# CH32X033SimpleBoard_SCH.net
KiCad netlist of a schematic drawn in EasyEDA Pro
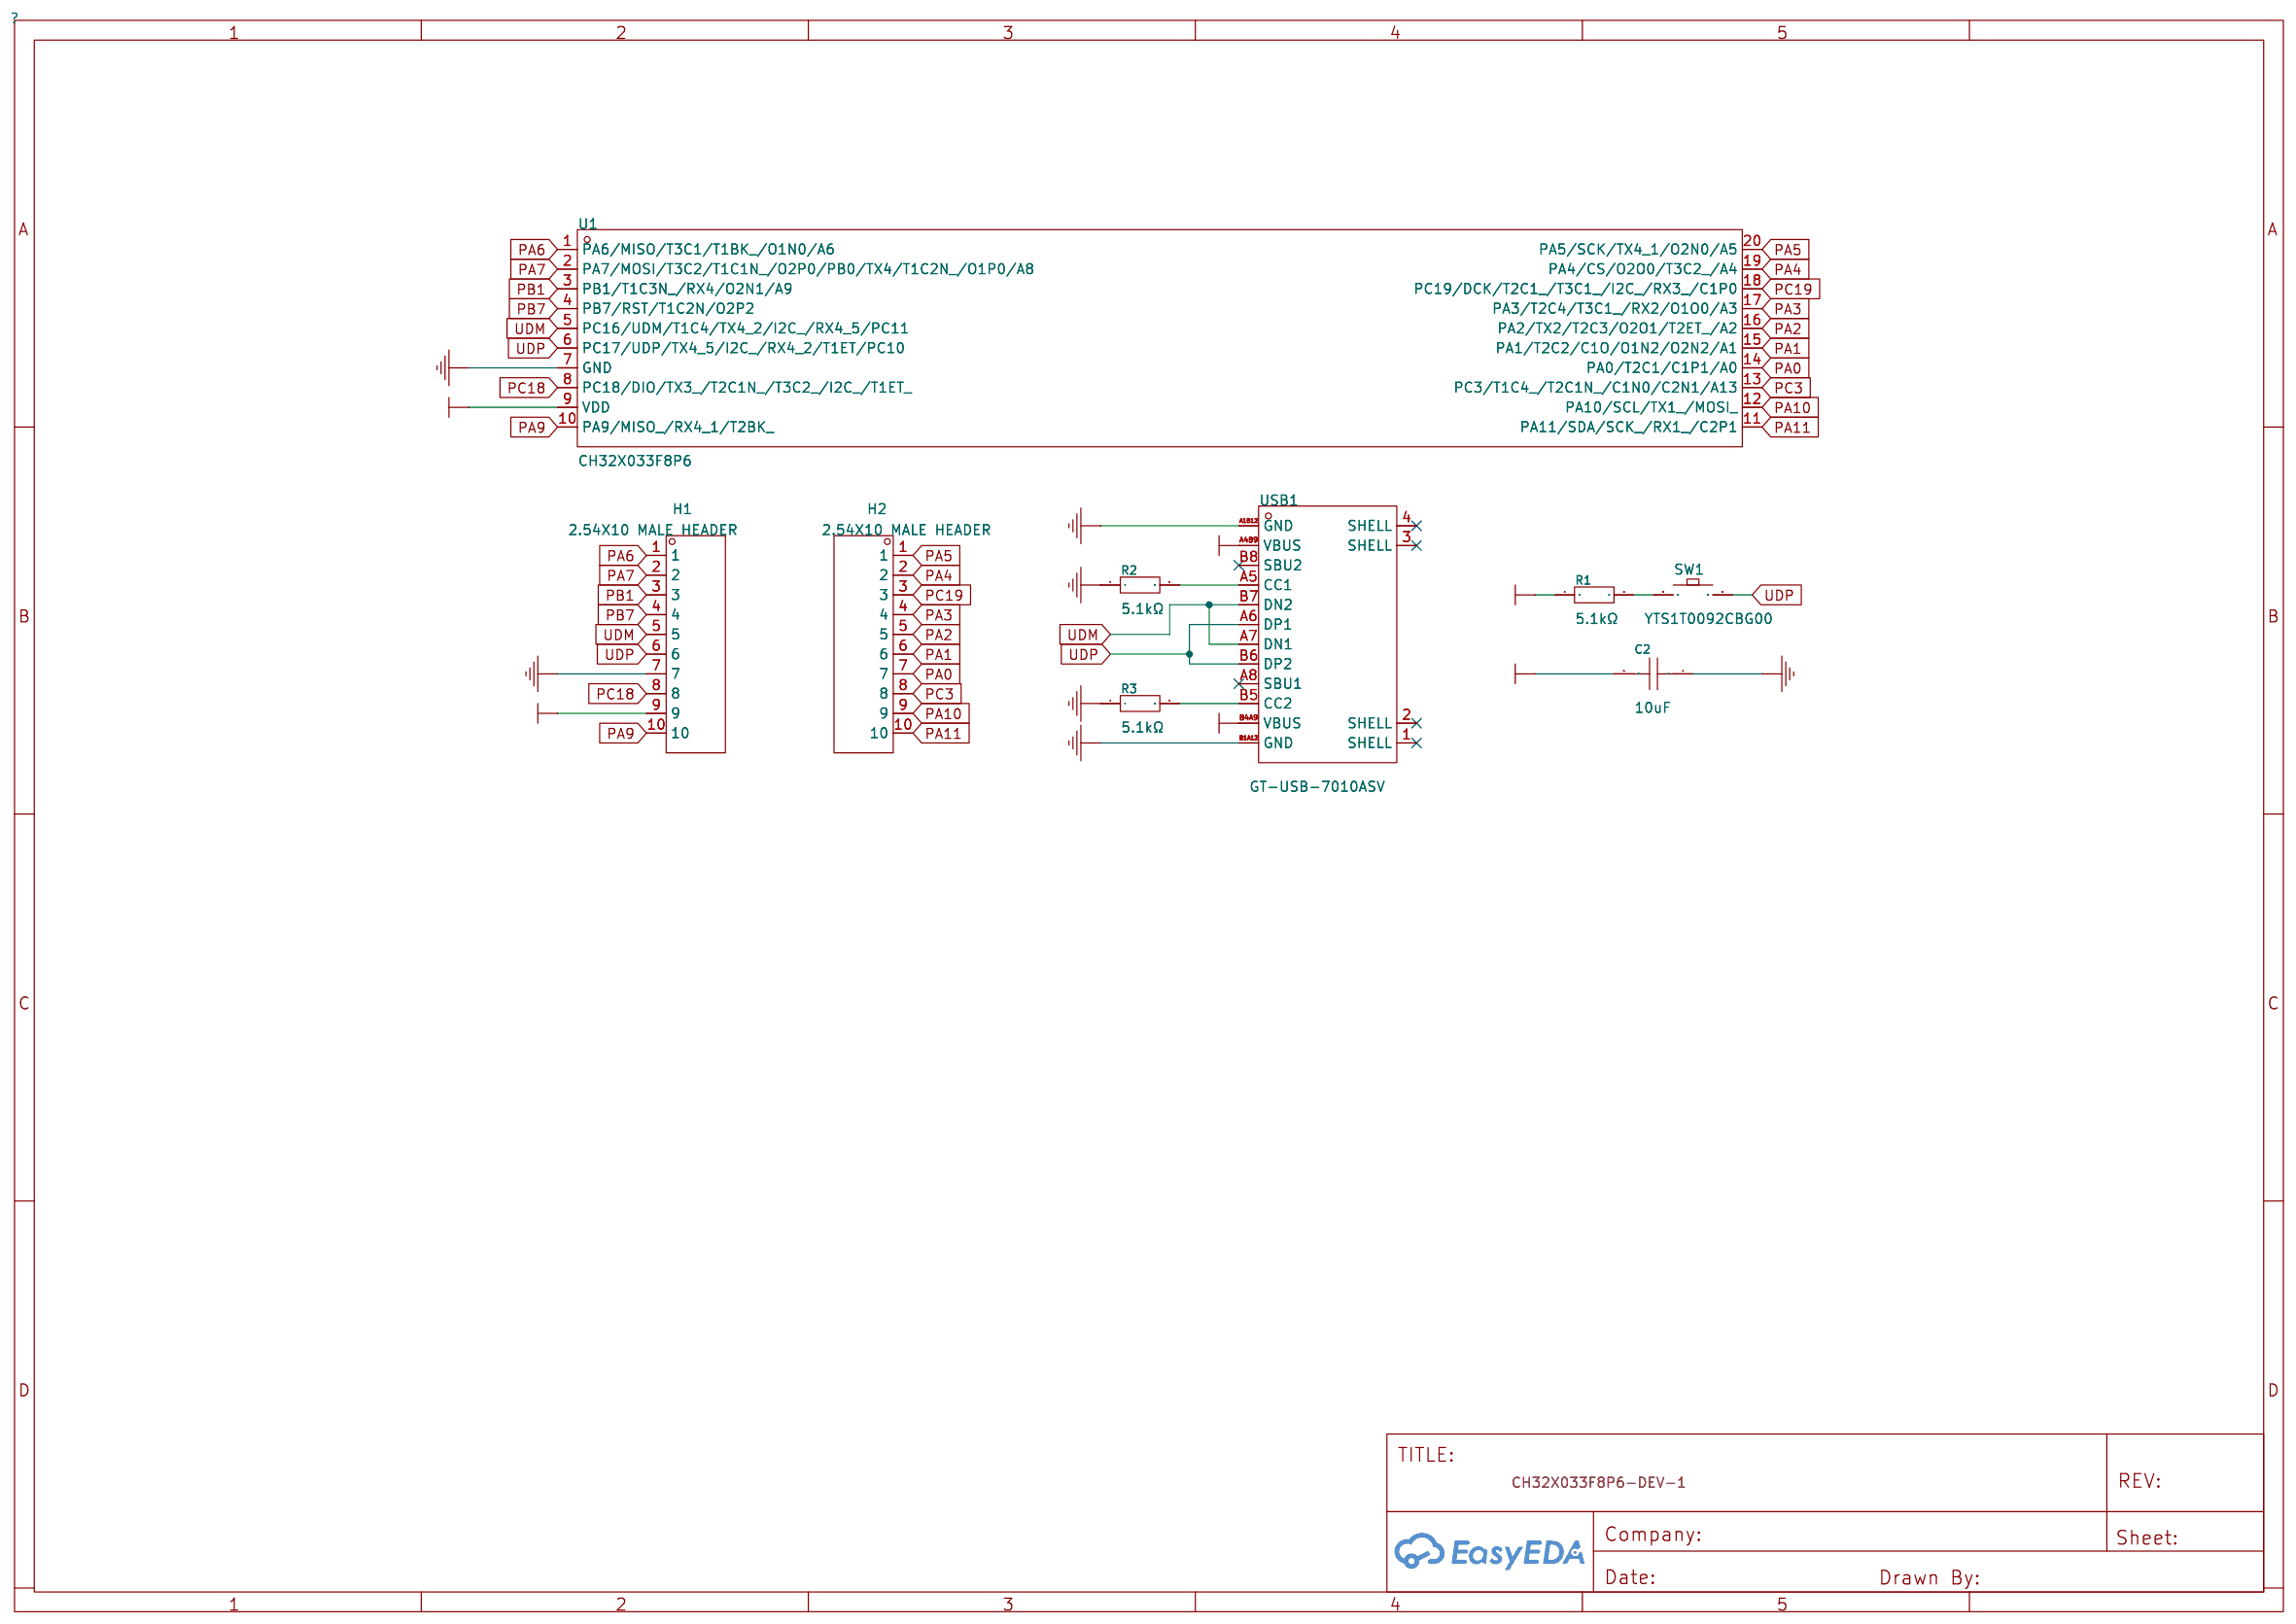
[diagram p0: schematic sheet]

(export (version "E")
  (design (tool "Eeschema 10.0.6"))
  (components
    (comp (ref "C2")
      (value "10uF")
      (footprint "easyedapro:C0603")
      (fields
        (field (name "Manufacturer Part") "CL10A106KP8NNNC")
        (field (name "Manufacturer") "SAMSUNG(三星)")
      )
      (libsource (lib "easyedapro") (part "CL10A106KP8NNNC"))
    )
    (comp (ref "H1")
      (value "2.54X10 MALE HEADER")
      (footprint "easyedapro:footprint_8cc6")
      (fields
        (field (name "Manufacturer Part") "210S-1*11P L=11.6MMGold-plated black")
        (field (name "Manufacturer") "Ckmtw")
      )
      (libsource (lib "easyedapro") (part "2.54X10 MALE HEADER"))
    )
    (comp (ref "H2")
      (value "2.54X10 MALE HEADER")
      (footprint "easyedapro:footprint_8cc6")
      (fields
        (field (name "Manufacturer Part") "210S-1*11P L=11.6MMGold-plated black")
        (field (name "Manufacturer") "Ckmtw")
      )
      (libsource (lib "") (part "2.54X10 MALE HEADER_1"))
    )
    (comp (ref "R1")
      (value "5.1kΩ")
      (footprint "easyedapro:R0603")
      (fields
        (field (name "Manufacturer Part") "0603WAF5101T5E")
        (field (name "Manufacturer") "UNI-ROYAL(厚声)")
      )
      (libsource (lib "easyedapro") (part "0603WAF5101T5E"))
    )
    (comp (ref "R2")
      (value "5.1kΩ")
      (footprint "easyedapro:R0603")
      (fields
        (field (name "Manufacturer Part") "0603WAF5101T5E")
        (field (name "Manufacturer") "UNI-ROYAL(厚声)")
      )
      (libsource (lib "easyedapro") (part "0603WAF5101T5E"))
    )
    (comp (ref "R3")
      (value "5.1kΩ")
      (footprint "easyedapro:R0603")
      (fields
        (field (name "Manufacturer Part") "0603WAF5101T5E")
        (field (name "Manufacturer") "UNI-ROYAL(厚声)")
      )
      (libsource (lib "easyedapro") (part "0603WAF5101T5E"))
    )
    (comp (ref "SW1")
      (value "YTS1T0092CBG00")
      (footprint "easyedapro:SW-SMD_L4.0-W2.9-LS5.0")
      (fields (field (name "Manufacturer") "YIYUAN(怡远)"))
      (libsource (lib "easyedapro") (part "BOOT"))
    )
    (comp (ref "U1")
      (value "CH32X033F8P6")
      (footprint "easyedapro:TSSOP-20_L6.5-W4.4-P0.65-LS6.4-BL")
      (fields (field (name "Manufacturer") "WCH(南京沁恒)"))
      (libsource (lib "easyedapro") (part "CH32X033F8P6"))
    )
    (comp (ref "USB1")
      (value "GT-USB-7010ASV")
      (footprint "easyedapro:USB-C-SMD_G-SWITCH_GT-USB-7010ASV")
      (fields (field (name "Manufacturer") "G-Switch(品赞)"))
      (libsource (lib "easyedapro") (part "GT-USB-7010ASV"))
    )
  )
  (nets
    (net (code "1") (name "+5V") (class "Default")
      (node (ref "C2") (pin "2") (pinfunction "2_2") (pintype "input"))
      (node (ref "H1") (pin "9") (pinfunction "9_9") (pintype "unspecified"))
      (node (ref "R1") (pin "1") (pinfunction "1_1") (pintype "input"))
      (node (ref "U1") (pin "9") (pinfunction "VDD_9") (pintype "unspecified"))
      (node (ref "USB1") (pin "A4B9") (pinfunction "VBUS_A4B9") (pintype "unspecified"))
      (node (ref "USB1") (pin "B4A9") (pinfunction "VBUS_B4A9") (pintype "unspecified"))
    )
    (net (code "2") (name "GND") (class "Default")
      (node (ref "C2") (pin "1") (pinfunction "1_1") (pintype "input"))
      (node (ref "H1") (pin "7") (pinfunction "7_7") (pintype "unspecified"))
      (node (ref "R2") (pin "1") (pinfunction "1_1") (pintype "input"))
      (node (ref "R3") (pin "1") (pinfunction "1_1") (pintype "input"))
      (node (ref "U1") (pin "7") (pinfunction "GND_7") (pintype "unspecified"))
      (node (ref "USB1") (pin "A1B12") (pinfunction "GND_A1B12") (pintype "unspecified"))
      (node (ref "USB1") (pin "B1A12") (pinfunction "GND_B1A12") (pintype "unspecified"))
    )
    (net (code "3") (name "Net-(R1-Pad2)") (class "Default")
      (node (ref "R1") (pin "2") (pinfunction "2_2") (pintype "input"))
      (node (ref "SW1") (pin "2") (pinfunction "2_2") (pintype "input"))
    )
    (net (code "4") (name "Net-(USB1-CC1)") (class "Default")
      (node (ref "R2") (pin "2") (pinfunction "2_2") (pintype "input"))
      (node (ref "USB1") (pin "A5") (pinfunction "CC1_A5") (pintype "unspecified"))
    )
    (net (code "5") (name "Net-(USB1-CC2)") (class "Default")
      (node (ref "R3") (pin "2") (pinfunction "2_2") (pintype "input"))
      (node (ref "USB1") (pin "B5") (pinfunction "CC2_B5") (pintype "unspecified"))
    )
    (net (code "6") (name "PA0") (class "Default")
      (node (ref "H2") (pin "7") (pinfunction "7_7") (pintype "unspecified"))
      (node (ref "U1") (pin "14") (pinfunction "PA0/T2C1/C1P1/A0_14") (pintype "unspecified"))
    )
    (net (code "7") (name "PA1") (class "Default")
      (node (ref "H2") (pin "6") (pinfunction "6_6") (pintype "unspecified"))
      (node (ref "U1") (pin "15") (pinfunction "PA1/T2C2/C1O/O1N2/O2N2/A1_15") (pintype "unspecified"))
    )
    (net (code "8") (name "PA2") (class "Default")
      (node (ref "H2") (pin "5") (pinfunction "5_5") (pintype "unspecified"))
      (node (ref "U1") (pin "16") (pinfunction "PA2/TX2/T2C3/O2O1/T2ET_/A2_16") (pintype "unspecified"))
    )
    (net (code "9") (name "PA3") (class "Default")
      (node (ref "H2") (pin "4") (pinfunction "4_4") (pintype "unspecified"))
      (node (ref "U1") (pin "17") (pinfunction "PA3/T2C4/T3C1_/RX2/O1O0/A3_17") (pintype "unspecified"))
    )
    (net (code "10") (name "PA4") (class "Default")
      (node (ref "H2") (pin "2") (pinfunction "2_2") (pintype "unspecified"))
      (node (ref "U1") (pin "19") (pinfunction "PA4/CS/O2O0/T3C2_/A4_19") (pintype "unspecified"))
    )
    (net (code "11") (name "PA5") (class "Default")
      (node (ref "H2") (pin "1") (pinfunction "1_1") (pintype "unspecified"))
      (node (ref "U1") (pin "20") (pinfunction "PA5/SCK/TX4_1/O2N0/A5_20") (pintype "unspecified"))
    )
    (net (code "12") (name "PA6") (class "Default")
      (node (ref "H1") (pin "1") (pinfunction "1_1") (pintype "unspecified"))
      (node (ref "U1") (pin "1") (pinfunction "PA6/MISO/T3C1/T1BK_/O1N0/A6_1") (pintype "unspecified"))
    )
    (net (code "13") (name "PA7") (class "Default")
      (node (ref "H1") (pin "2") (pinfunction "2_2") (pintype "unspecified"))
      (node (ref "U1") (pin "2") (pinfunction "PA7/MOSI/T3C2/T1C1N_/O2P0/PB0/TX4/T1C2N_/O1P0/A8_2") (pintype "unspecified"))
    )
    (net (code "14") (name "PA9") (class "Default")
      (node (ref "H1") (pin "10") (pinfunction "10_10") (pintype "unspecified"))
      (node (ref "U1") (pin "10") (pinfunction "PA9/MISO_/RX4_1/T2BK__10") (pintype "unspecified"))
    )
    (net (code "15") (name "PA10") (class "Default")
      (node (ref "H2") (pin "9") (pinfunction "9_9") (pintype "unspecified"))
      (node (ref "U1") (pin "12") (pinfunction "PA10/SCL/TX1_/MOSI__12") (pintype "unspecified"))
    )
    (net (code "16") (name "PA11") (class "Default")
      (node (ref "H2") (pin "10") (pinfunction "10_10") (pintype "unspecified"))
      (node (ref "U1") (pin "11") (pinfunction "PA11/SDA/SCK_/RX1_/C2P1_11") (pintype "unspecified"))
    )
    (net (code "17") (name "PB1") (class "Default")
      (node (ref "H1") (pin "3") (pinfunction "3_3") (pintype "unspecified"))
      (node (ref "U1") (pin "3") (pinfunction "PB1/T1C3N_/RX4/O2N1/A9_3") (pintype "unspecified"))
    )
    (net (code "18") (name "PB7") (class "Default")
      (node (ref "H1") (pin "4") (pinfunction "4_4") (pintype "unspecified"))
      (node (ref "U1") (pin "4") (pinfunction "PB7/RST/T1C2N/O2P2_4") (pintype "unspecified"))
    )
    (net (code "19") (name "PC3") (class "Default")
      (node (ref "H2") (pin "8") (pinfunction "8_8") (pintype "unspecified"))
      (node (ref "U1") (pin "13") (pinfunction "PC3/T1C4_/T2C1N_/C1N0/C2N1/A13_13") (pintype "unspecified"))
    )
    (net (code "20") (name "PC18") (class "Default")
      (node (ref "H1") (pin "8") (pinfunction "8_8") (pintype "unspecified"))
      (node (ref "U1") (pin "8") (pinfunction "PC18/DIO/TX3_/T2C1N_/T3C2_/I2C_/T1ET__8") (pintype "unspecified"))
    )
    (net (code "21") (name "PC19") (class "Default")
      (node (ref "H2") (pin "3") (pinfunction "3_3") (pintype "unspecified"))
      (node (ref "U1") (pin "18") (pinfunction "PC19/DCK/T2C1_/T3C1_/I2C_/RX3_/C1P0_18") (pintype "unspecified"))
    )
    (net (code "22") (name "UDM") (class "Default")
      (node (ref "H1") (pin "5") (pinfunction "5_5") (pintype "unspecified"))
      (node (ref "U1") (pin "5") (pinfunction "PC16/UDM/T1C4/TX4_2/I2C_/RX4_5/PC11_5") (pintype "unspecified"))
      (node (ref "USB1") (pin "A7") (pinfunction "DN1_A7") (pintype "unspecified"))
      (node (ref "USB1") (pin "B7") (pinfunction "DN2_B7") (pintype "unspecified"))
    )
    (net (code "23") (name "UDP") (class "Default")
      (node (ref "H1") (pin "6") (pinfunction "6_6") (pintype "unspecified"))
      (node (ref "SW1") (pin "1") (pinfunction "1_1") (pintype "input"))
      (node (ref "U1") (pin "6") (pinfunction "PC17/UDP/TX4_5/I2C_/RX4_2/T1ET/PC10_6") (pintype "unspecified"))
      (node (ref "USB1") (pin "A6") (pinfunction "DP1_A6") (pintype "unspecified"))
      (node (ref "USB1") (pin "B6") (pinfunction "DP2_B6") (pintype "unspecified"))
    )
    (net (code "24") (name "unconnected-(USB1-SBU1-PadA8)") (class "Default")
      (node (ref "USB1") (pin "A8") (pinfunction "SBU1_A8") (pintype "unspecified+no_connect"))
    )
    (net (code "25") (name "unconnected-(USB1-SBU2-PadB8)") (class "Default")
      (node (ref "USB1") (pin "B8") (pinfunction "SBU2_B8") (pintype "unspecified+no_connect"))
    )
    (net (code "26") (name "unconnected-(USB1-SHELL-Pad1)") (class "Default")
      (node (ref "USB1") (pin "1") (pinfunction "SHELL_1") (pintype "unspecified+no_connect"))
    )
    (net (code "27") (name "unconnected-(USB1-SHELL-Pad2)") (class "Default")
      (node (ref "USB1") (pin "2") (pinfunction "SHELL_2") (pintype "unspecified+no_connect"))
    )
    (net (code "28") (name "unconnected-(USB1-SHELL-Pad3)") (class "Default")
      (node (ref "USB1") (pin "3") (pinfunction "SHELL_3") (pintype "unspecified+no_connect"))
    )
    (net (code "29") (name "unconnected-(USB1-SHELL-Pad4)") (class "Default")
      (node (ref "USB1") (pin "4") (pinfunction "SHELL_4") (pintype "unspecified+no_connect"))
    )
  )
)
